# mainSheet.net
KiCad netlist of a schematic drawn in Altium Designer
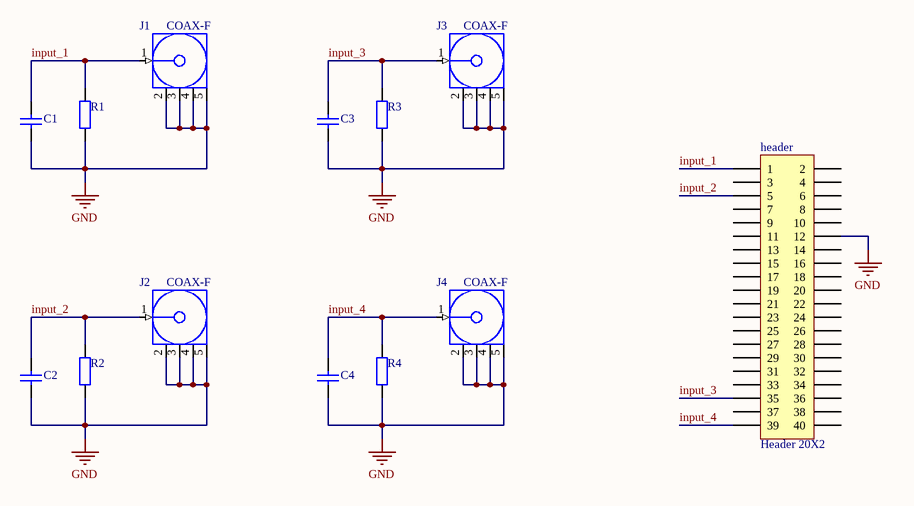
[diagram p0: mainSheet.SchDoc]

(export (version "E")
  (design (tool "Eeschema 10.0.6"))
  (components
    (comp (ref "C1")
      (value "Cap")
      (footprint "RAD-0.3")
      (description "Capacitor")
      (fields (field (name "PUBLISHER") "Altium Limited"))
      (libsource (lib "Miscellaneous Devices") (part "Cap"))
    )
    (comp (ref "C2")
      (value "Cap")
      (footprint "RAD-0.3")
      (description "Capacitor")
      (fields (field (name "PUBLISHER") "Altium Limited"))
      (libsource (lib "Miscellaneous Devices") (part "Cap"))
    )
    (comp (ref "C3")
      (value "Cap")
      (footprint "RAD-0.3")
      (description "Capacitor")
      (fields (field (name "PUBLISHER") "Altium Limited"))
      (libsource (lib "Miscellaneous Devices") (part "Cap"))
    )
    (comp (ref "C4")
      (value "Cap")
      (footprint "RAD-0.3")
      (description "Capacitor")
      (fields (field (name "PUBLISHER") "Altium Limited"))
      (libsource (lib "Miscellaneous Devices") (part "Cap"))
    )
    (comp (ref "header")
      (value "Header 20X2")
      (footprint "HDR2X20")
      (description "Header, 20-Pin, Dual row")
      (fields (field (name "PUBLISHER") "Altium Limited"))
      (libsource (lib "Miscellaneous Connectors") (part "Header 20X2"))
    )
    (comp (ref "J1")
      (value "COAX-F")
      (footprint "bnc50_5pins")
      (fields (field (name "PUBLISHER") "Altium Limited"))
      (libsource (lib "Miscellaneous Connectors") (part "COAX-F"))
    )
    (comp (ref "J2")
      (value "COAX-F")
      (footprint "bnc50_5pins")
      (fields (field (name "PUBLISHER") "Altium Limited"))
      (libsource (lib "Miscellaneous Connectors") (part "COAX-F"))
    )
    (comp (ref "J3")
      (value "COAX-F")
      (footprint "bnc50_5pins")
      (fields (field (name "PUBLISHER") "Altium Limited"))
      (libsource (lib "Miscellaneous Connectors") (part "COAX-F"))
    )
    (comp (ref "J4")
      (value "COAX-F")
      (footprint "bnc50_5pins")
      (fields (field (name "PUBLISHER") "Altium Limited"))
      (libsource (lib "Miscellaneous Connectors") (part "COAX-F"))
    )
    (comp (ref "R1")
      (value "Res2")
      (footprint "AXIAL-0.4")
      (description "Resistor")
      (fields (field (name "PUBLISHER") "Altium Limited"))
      (libsource (lib "Miscellaneous Devices") (part "Res2"))
    )
    (comp (ref "R2")
      (value "Res2")
      (footprint "AXIAL-0.4")
      (description "Resistor")
      (fields (field (name "PUBLISHER") "Altium Limited"))
      (libsource (lib "Miscellaneous Devices") (part "Res2"))
    )
    (comp (ref "R3")
      (value "Res2")
      (footprint "AXIAL-0.4")
      (description "Resistor")
      (fields (field (name "PUBLISHER") "Altium Limited"))
      (libsource (lib "Miscellaneous Devices") (part "Res2"))
    )
    (comp (ref "R4")
      (value "Res2")
      (footprint "AXIAL-0.4")
      (description "Resistor")
      (fields (field (name "PUBLISHER") "Altium Limited"))
      (libsource (lib "Miscellaneous Devices") (part "Res2"))
    )
  )
  (nets
    (net (code "1") (name "/input_1") (class "Default")
      (node (ref "C1") (pin "2") (pinfunction "2_2") (pintype "passive"))
      (node (ref "J1") (pin "1") (pinfunction "Signal_1") (pintype "input"))
      (node (ref "R1") (pin "2") (pinfunction "2_2") (pintype "passive"))
      (node (ref "header") (pin "1") (pinfunction "1_1") (pintype "passive"))
    )
    (net (code "2") (name "/input_2") (class "Default")
      (node (ref "C2") (pin "2") (pinfunction "2_2") (pintype "passive"))
      (node (ref "J2") (pin "1") (pinfunction "Signal_1") (pintype "input"))
      (node (ref "R2") (pin "2") (pinfunction "2_2") (pintype "passive"))
      (node (ref "header") (pin "5") (pinfunction "5_5") (pintype "passive"))
    )
    (net (code "3") (name "/input_3") (class "Default")
      (node (ref "C3") (pin "2") (pinfunction "2_2") (pintype "passive"))
      (node (ref "J3") (pin "1") (pinfunction "Signal_1") (pintype "input"))
      (node (ref "R3") (pin "2") (pinfunction "2_2") (pintype "passive"))
      (node (ref "header") (pin "35") (pinfunction "35_35") (pintype "passive"))
    )
    (net (code "4") (name "/input_4") (class "Default")
      (node (ref "C4") (pin "2") (pinfunction "2_2") (pintype "passive"))
      (node (ref "J4") (pin "1") (pinfunction "Signal_1") (pintype "input"))
      (node (ref "R4") (pin "2") (pinfunction "2_2") (pintype "passive"))
      (node (ref "header") (pin "39") (pinfunction "39_39") (pintype "passive"))
    )
    (net (code "5") (name "GND") (class "Default")
      (node (ref "C1") (pin "1") (pinfunction "1_1") (pintype "passive"))
      (node (ref "C2") (pin "1") (pinfunction "1_1") (pintype "passive"))
      (node (ref "C3") (pin "1") (pinfunction "1_1") (pintype "passive"))
      (node (ref "C4") (pin "1") (pinfunction "1_1") (pintype "passive"))
      (node (ref "J1") (pin "2") (pinfunction "GND_2") (pintype "power_in"))
      (node (ref "J1") (pin "3") (pinfunction "GND_3") (pintype "power_in"))
      (node (ref "J1") (pin "4") (pinfunction "GND_4") (pintype "power_in"))
      (node (ref "J1") (pin "5") (pinfunction "GND_5") (pintype "power_in"))
      (node (ref "J2") (pin "2") (pinfunction "GND_2") (pintype "power_in"))
      (node (ref "J2") (pin "3") (pinfunction "GND_3") (pintype "power_in"))
      (node (ref "J2") (pin "4") (pinfunction "GND_4") (pintype "power_in"))
      (node (ref "J2") (pin "5") (pinfunction "GND_5") (pintype "power_in"))
      (node (ref "J3") (pin "2") (pinfunction "GND_2") (pintype "power_in"))
      (node (ref "J3") (pin "3") (pinfunction "GND_3") (pintype "power_in"))
      (node (ref "J3") (pin "4") (pinfunction "GND_4") (pintype "power_in"))
      (node (ref "J3") (pin "5") (pinfunction "GND_5") (pintype "power_in"))
      (node (ref "J4") (pin "2") (pinfunction "GND_2") (pintype "power_in"))
      (node (ref "J4") (pin "3") (pinfunction "GND_3") (pintype "power_in"))
      (node (ref "J4") (pin "4") (pinfunction "GND_4") (pintype "power_in"))
      (node (ref "J4") (pin "5") (pinfunction "GND_5") (pintype "power_in"))
      (node (ref "R1") (pin "1") (pinfunction "1_1") (pintype "passive"))
      (node (ref "R2") (pin "1") (pinfunction "1_1") (pintype "passive"))
      (node (ref "R3") (pin "1") (pinfunction "1_1") (pintype "passive"))
      (node (ref "R4") (pin "1") (pinfunction "1_1") (pintype "passive"))
      (node (ref "header") (pin "12") (pinfunction "12_12") (pintype "passive"))
    )
    (net (code "6") (name "unconnected-(header-Pad2)") (class "Default")
      (node (ref "header") (pin "2") (pinfunction "2_2") (pintype "passive"))
    )
    (net (code "7") (name "unconnected-(header-Pad3)") (class "Default")
      (node (ref "header") (pin "3") (pinfunction "3_3") (pintype "passive"))
    )
    (net (code "8") (name "unconnected-(header-Pad4)") (class "Default")
      (node (ref "header") (pin "4") (pinfunction "4_4") (pintype "passive"))
    )
    (net (code "9") (name "unconnected-(header-Pad6)") (class "Default")
      (node (ref "header") (pin "6") (pinfunction "6_6") (pintype "passive"))
    )
    (net (code "10") (name "unconnected-(header-Pad7)") (class "Default")
      (node (ref "header") (pin "7") (pinfunction "7_7") (pintype "passive"))
    )
    (net (code "11") (name "unconnected-(header-Pad8)") (class "Default")
      (node (ref "header") (pin "8") (pinfunction "8_8") (pintype "passive"))
    )
    (net (code "12") (name "unconnected-(header-Pad9)") (class "Default")
      (node (ref "header") (pin "9") (pinfunction "9_9") (pintype "passive"))
    )
    (net (code "13") (name "unconnected-(header-Pad10)") (class "Default")
      (node (ref "header") (pin "10") (pinfunction "10_10") (pintype "passive"))
    )
    (net (code "14") (name "unconnected-(header-Pad11)") (class "Default")
      (node (ref "header") (pin "11") (pinfunction "11_11") (pintype "passive"))
    )
    (net (code "15") (name "unconnected-(header-Pad13)") (class "Default")
      (node (ref "header") (pin "13") (pinfunction "13_13") (pintype "passive"))
    )
    (net (code "16") (name "unconnected-(header-Pad14)") (class "Default")
      (node (ref "header") (pin "14") (pinfunction "14_14") (pintype "passive"))
    )
    (net (code "17") (name "unconnected-(header-Pad15)") (class "Default")
      (node (ref "header") (pin "15") (pinfunction "15_15") (pintype "passive"))
    )
    (net (code "18") (name "unconnected-(header-Pad16)") (class "Default")
      (node (ref "header") (pin "16") (pinfunction "16_16") (pintype "passive"))
    )
    (net (code "19") (name "unconnected-(header-Pad17)") (class "Default")
      (node (ref "header") (pin "17") (pinfunction "17_17") (pintype "passive"))
    )
    (net (code "20") (name "unconnected-(header-Pad18)") (class "Default")
      (node (ref "header") (pin "18") (pinfunction "18_18") (pintype "passive"))
    )
    (net (code "21") (name "unconnected-(header-Pad19)") (class "Default")
      (node (ref "header") (pin "19") (pinfunction "19_19") (pintype "passive"))
    )
    (net (code "22") (name "unconnected-(header-Pad20)") (class "Default")
      (node (ref "header") (pin "20") (pinfunction "20_20") (pintype "passive"))
    )
    (net (code "23") (name "unconnected-(header-Pad21)") (class "Default")
      (node (ref "header") (pin "21") (pinfunction "21_21") (pintype "passive"))
    )
    (net (code "24") (name "unconnected-(header-Pad22)") (class "Default")
      (node (ref "header") (pin "22") (pinfunction "22_22") (pintype "passive"))
    )
    (net (code "25") (name "unconnected-(header-Pad23)") (class "Default")
      (node (ref "header") (pin "23") (pinfunction "23_23") (pintype "passive"))
    )
    (net (code "26") (name "unconnected-(header-Pad24)") (class "Default")
      (node (ref "header") (pin "24") (pinfunction "24_24") (pintype "passive"))
    )
    (net (code "27") (name "unconnected-(header-Pad25)") (class "Default")
      (node (ref "header") (pin "25") (pinfunction "25_25") (pintype "passive"))
    )
    (net (code "28") (name "unconnected-(header-Pad26)") (class "Default")
      (node (ref "header") (pin "26") (pinfunction "26_26") (pintype "passive"))
    )
    (net (code "29") (name "unconnected-(header-Pad27)") (class "Default")
      (node (ref "header") (pin "27") (pinfunction "27_27") (pintype "passive"))
    )
    (net (code "30") (name "unconnected-(header-Pad28)") (class "Default")
      (node (ref "header") (pin "28") (pinfunction "28_28") (pintype "passive"))
    )
    (net (code "31") (name "unconnected-(header-Pad29)") (class "Default")
      (node (ref "header") (pin "29") (pinfunction "29_29") (pintype "passive"))
    )
    (net (code "32") (name "unconnected-(header-Pad30)") (class "Default")
      (node (ref "header") (pin "30") (pinfunction "30_30") (pintype "passive"))
    )
    (net (code "33") (name "unconnected-(header-Pad31)") (class "Default")
      (node (ref "header") (pin "31") (pinfunction "31_31") (pintype "passive"))
    )
    (net (code "34") (name "unconnected-(header-Pad32)") (class "Default")
      (node (ref "header") (pin "32") (pinfunction "32_32") (pintype "passive"))
    )
    (net (code "35") (name "unconnected-(header-Pad33)") (class "Default")
      (node (ref "header") (pin "33") (pinfunction "33_33") (pintype "passive"))
    )
    (net (code "36") (name "unconnected-(header-Pad34)") (class "Default")
      (node (ref "header") (pin "34") (pinfunction "34_34") (pintype "passive"))
    )
    (net (code "37") (name "unconnected-(header-Pad36)") (class "Default")
      (node (ref "header") (pin "36") (pinfunction "36_36") (pintype "passive"))
    )
    (net (code "38") (name "unconnected-(header-Pad37)") (class "Default")
      (node (ref "header") (pin "37") (pinfunction "37_37") (pintype "passive"))
    )
    (net (code "39") (name "unconnected-(header-Pad38)") (class "Default")
      (node (ref "header") (pin "38") (pinfunction "38_38") (pintype "passive"))
    )
    (net (code "40") (name "unconnected-(header-Pad40)") (class "Default")
      (node (ref "header") (pin "40") (pinfunction "40_40") (pintype "passive"))
    )
  )
)
